# DIS_SENSOR.net
KiCad netlist of a schematic drawn in Altium Designer
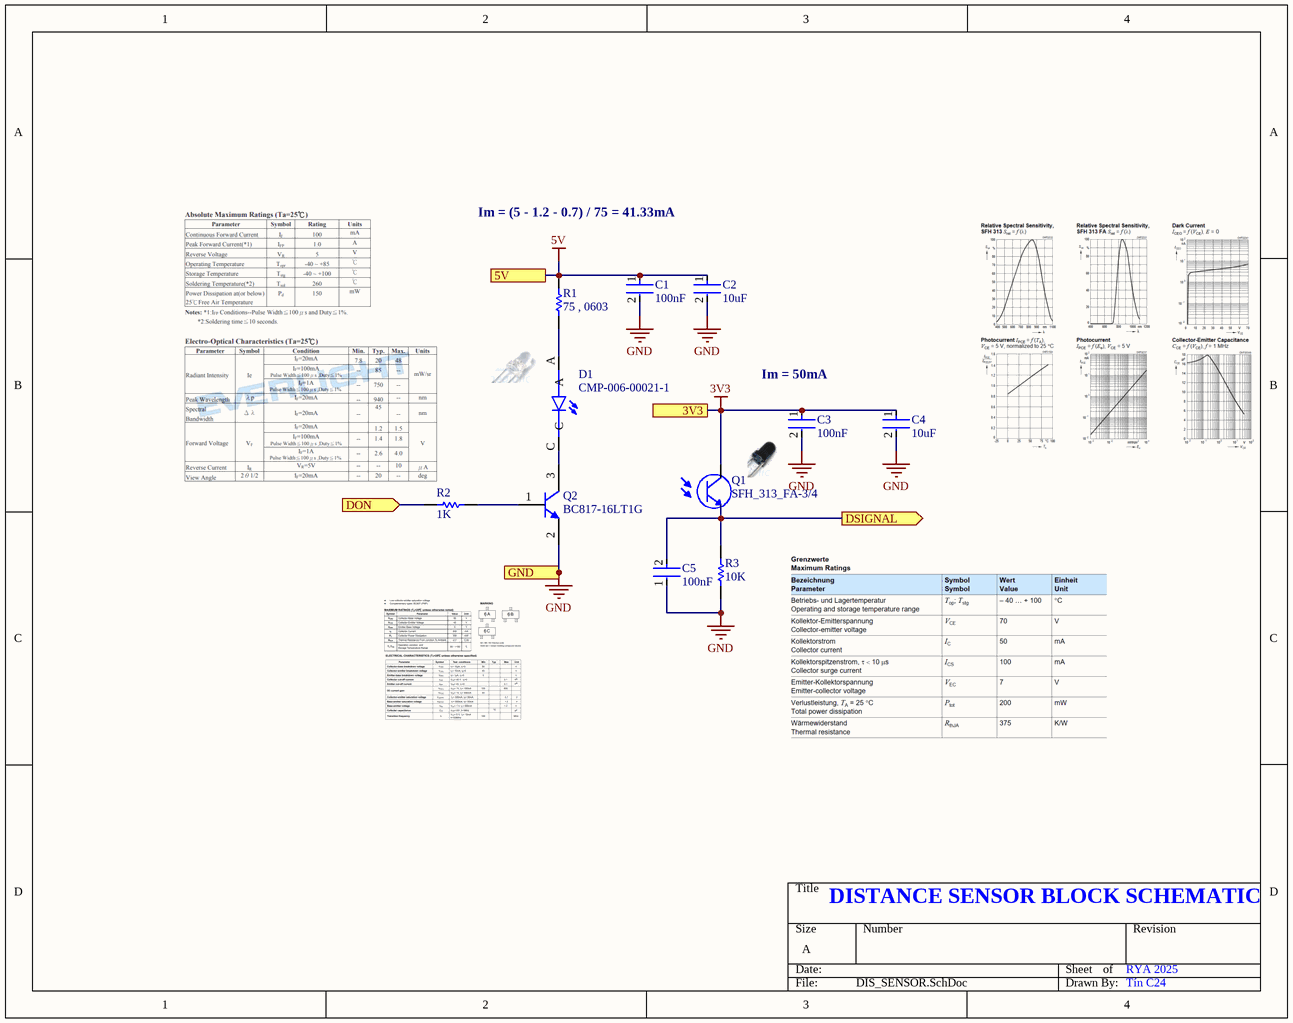
[diagram p0: DIS_SENSOR.SchDoc]

(export (version "E")
  (design (tool "Eeschema 10.0.6"))
  (components
    (comp (ref "C1")
      (value "100nF")
      (footprint "FP-C0603C-CF-MFG")
      (description "CAP CER 20PF 50V 5% NP0 0603")
      (fields
        (field (name "MANUFACTURER PART NUMBER") "C0603C200J5GACTU")
        (field (name "MANUFACTURER") "KEMET")
      )
      (libsource (lib "Altium Content Vault") (part "b4654b650e69147ec39a6b967a45e02"))
    )
    (comp (ref "C2")
      (value "10uF")
      (footprint "FP-C0603C-CF-MFG")
      (description "CAP CER 20PF 50V 5% NP0 0603")
      (fields
        (field (name "MANUFACTURER PART NUMBER") "C0603C200J5GACTU")
        (field (name "MANUFACTURER") "KEMET")
      )
      (libsource (lib "Altium Content Vault") (part "b4654b650e69147ec39a6b967a45e02"))
    )
    (comp (ref "C3")
      (value "100nF")
      (footprint "FP-C0603C-CF-MFG")
      (description "CAP CER 20PF 50V 5% NP0 0603")
      (fields
        (field (name "MANUFACTURER PART NUMBER") "C0603C200J5GACTU")
        (field (name "MANUFACTURER") "KEMET")
      )
      (libsource (lib "Altium Content Vault") (part "b4654b650e69147ec39a6b967a45e02"))
    )
    (comp (ref "C4")
      (value "10uF")
      (footprint "FP-C0603C-CF-MFG")
      (description "CAP CER 20PF 50V 5% NP0 0603")
      (fields
        (field (name "MANUFACTURER PART NUMBER") "C0603C200J5GACTU")
        (field (name "MANUFACTURER") "KEMET")
      )
      (libsource (lib "Altium Content Vault") (part "b4654b650e69147ec39a6b967a45e02"))
    )
    (comp (ref "C5")
      (value "100nF")
      (footprint "FP-GRM15-MFG")
      (description "CAP CER 0.1UF 16V X7R 0402")
      (fields (field (name "MANUFACTURER PART NUMBER") "GRM155R71C104KA88D") (field (name "TOLERANCE") "10%"))
      (libsource (lib "Altium Content Vault") (part "236180d848d6139a670b325ea6854c9"))
    )
    (comp (ref "D1")
      (value "CMP-006-00021-1")
      (footprint "LED_WP7113SRC/DU")
      (description "Red 640nm LED Indication - Discrete 1.85V Radial")
      (fields (field (name "MP") "WP7113SRC/DU") (field (name "MF") "Kingbright"))
      (libsource (lib "Tin Tran") (part "WP7113SRC/DU"))
    )
    (comp (ref "Q1")
      (value "SFH_313_FA-3/4")
      (footprint "XDCR_SFH_313_FA-3/4")
      (description "Phototransistors 870nm Top View Radial - 2 Leads")
      (fields (field (name "MF") "OSRAM Opto") (field (name "DIGI-KEY_PART_NUMBER") "475-3328-ND"))
      (libsource (lib "SFH_313_FA-3_4") (part "SFH_313_FA-3/4"))
    )
    (comp (ref "Q2")
      (value "BC817-16LT1G")
      (footprint "ONSC-SOT-23-3-318-08_V")
      (description "General Purpose Transistor, NPN Silicon, 3-Pin SOT-23, Pb-Free, Tape and Reel")
      (fields (field (name "MANUFACTURER") "On Semiconductor"))
      (libsource (lib "Altium Content Vault") (part "ONSC-NPN-B1E2C3-3"))
    )
    (comp (ref "R1")
      (value "75 , 0603")
      (footprint "RESC1608X55X25LL10T15")
      (fields (field (name "TOLERANCE") "1%") (field (name "MANUFACTURER") "Yageo"))
      (libsource (lib "Altium Content Vault") (part "RES-2"))
    )
    (comp (ref "R2")
      (value "1K")
      (footprint "RESC1005X40X25LL05T05")
      (description "0402 , 1KOhm")
      (fields (field (name "MANUFACTURER") "Panasonic") (field (name "TOLERANCE") "5%"))
      (libsource (lib "Altium Content Vault") (part "RES-2"))
    )
    (comp (ref "R3")
      (value "10K")
      (footprint "RESC1005X40X25LL05T05")
      (description "Chip Resistor, 0 Ohm, 0.1 W, -55 to 155 degC, 0402 (1005 Metric), RoHS, Tape and Reel")
      (fields (field (name "MANUFACTURER") "Panasonic") (field (name "TOLERANCE") "5%"))
      (libsource (lib "Altium Content Vault") (part "RES-2"))
    )
  )
  (nets
    (net (code "1") (name "/DON") (class "Default")
      (node (ref "R2") (pin "2") (pinfunction "2_2") (pintype "passive"))
    )
    (net (code "2") (name "/DSIGNAL") (class "Default")
      (node (ref "C5") (pin "2") (pinfunction "2_2") (pintype "passive"))
      (node (ref "Q1") (pin "1") (pinfunction "E_1") (pintype "passive"))
      (node (ref "R3") (pin "1") (pinfunction "1_1") (pintype "passive"))
    )
    (net (code "3") (name "3V3") (class "Default")
      (node (ref "C3") (pin "1") (pinfunction "1_1") (pintype "passive"))
      (node (ref "C4") (pin "1") (pinfunction "1_1") (pintype "passive"))
      (node (ref "Q1") (pin "2") (pinfunction "C_2") (pintype "passive"))
    )
    (net (code "4") (name "5V") (class "Default")
      (node (ref "C1") (pin "1") (pinfunction "1_1") (pintype "passive"))
      (node (ref "C2") (pin "1") (pinfunction "1_1") (pintype "passive"))
      (node (ref "R1") (pin "2") (pinfunction "2_2") (pintype "passive"))
    )
    (net (code "5") (name "GND") (class "Default")
      (node (ref "C1") (pin "2") (pinfunction "2_2") (pintype "passive"))
      (node (ref "C2") (pin "2") (pinfunction "2_2") (pintype "passive"))
      (node (ref "C3") (pin "2") (pinfunction "2_2") (pintype "passive"))
      (node (ref "C4") (pin "2") (pinfunction "2_2") (pintype "passive"))
      (node (ref "C5") (pin "1") (pinfunction "1_1") (pintype "passive"))
      (node (ref "Q2") (pin "2") (pinfunction "E_2") (pintype "passive"))
      (node (ref "R3") (pin "2") (pinfunction "2_2") (pintype "passive"))
    )
    (net (code "6") (name "Net-(D1-PadA)") (class "Default")
      (node (ref "D1") (pin "A") (pinfunction "A_A") (pintype "passive"))
      (node (ref "R1") (pin "1") (pinfunction "1_1") (pintype "passive"))
    )
    (net (code "7") (name "Net-(Q2-B)") (class "Default")
      (node (ref "Q2") (pin "1") (pinfunction "B_1") (pintype "passive"))
      (node (ref "R2") (pin "1") (pinfunction "1_1") (pintype "passive"))
    )
    (net (code "8") (name "Net-(Q2-C)") (class "Default")
      (node (ref "D1") (pin "C") (pinfunction "C_C") (pintype "passive"))
      (node (ref "Q2") (pin "3") (pinfunction "C_3") (pintype "passive"))
    )
  )
)
